# nfc-epd-eink.net
KiCad netlist of a schematic drawn in Altium Designer
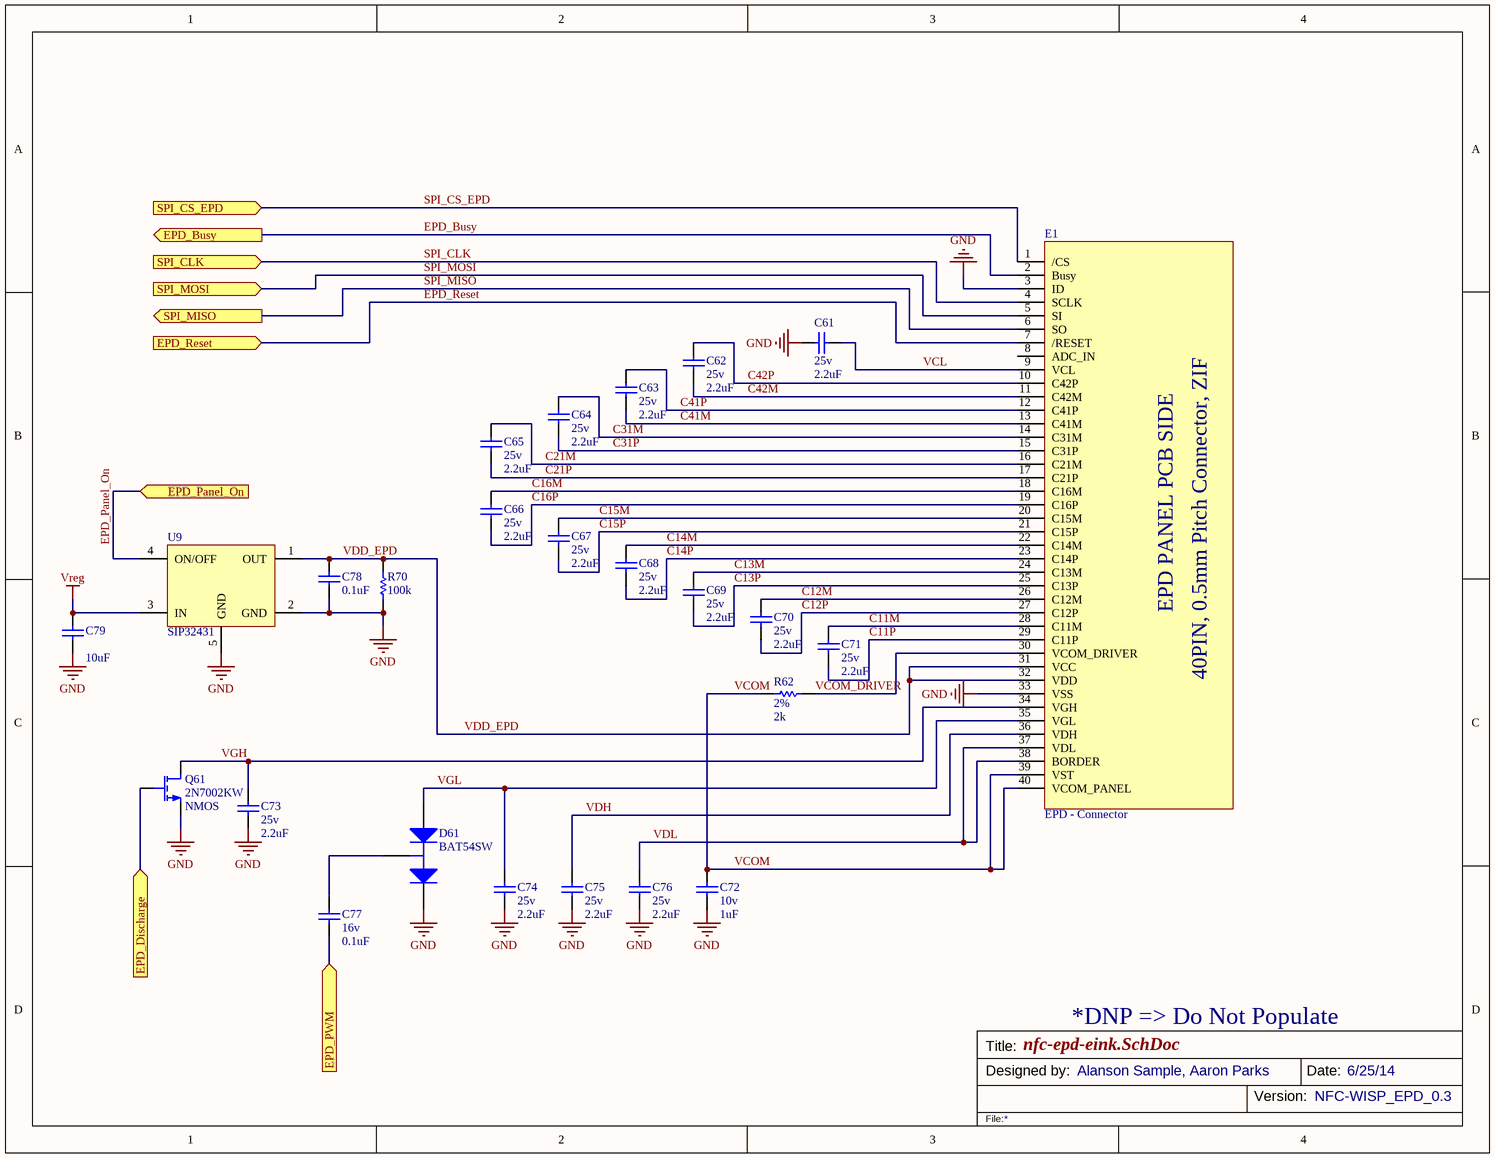
[diagram p0: nfc-epd-eink.SchDoc]

(export (version "E")
  (design (tool "Eeschema 10.0.6"))
  (components
    (comp (ref "C61")
      (value "2.2uF")
      (footprint "0402")
      (description "Ceramic Capacitor (Surface Mount)")
      (fields
        (field (name "MANUFACTURER") "Generic Ceramic Chip Cap (TBD)")
        (field (name "RATING") "25v")
        (field (name "Comment") "Cap")
      )
      (libsource (lib "WISP_AD10") (part "Cap"))
    )
    (comp (ref "C62")
      (value "2.2uF")
      (footprint "0402")
      (description "Ceramic Capacitor (Surface Mount)")
      (fields
        (field (name "MANUFACTURER") "Generic Ceramic Chip Cap (TBD)")
        (field (name "RATING") "25v")
        (field (name "Comment") "Cap")
      )
      (libsource (lib "WISP_AD10") (part "Cap"))
    )
    (comp (ref "C63")
      (value "2.2uF")
      (footprint "0402")
      (description "Ceramic Capacitor (Surface Mount)")
      (fields
        (field (name "MANUFACTURER") "Generic Ceramic Chip Cap (TBD)")
        (field (name "RATING") "25v")
        (field (name "Comment") "Cap")
      )
      (libsource (lib "WISP_AD10") (part "Cap"))
    )
    (comp (ref "C64")
      (value "2.2uF")
      (footprint "0402")
      (description "Ceramic Capacitor (Surface Mount)")
      (fields
        (field (name "MANUFACTURER") "Generic Ceramic Chip Cap (TBD)")
        (field (name "RATING") "25v")
        (field (name "Comment") "Cap")
      )
      (libsource (lib "WISP_AD10") (part "Cap"))
    )
    (comp (ref "C65")
      (value "2.2uF")
      (footprint "0402")
      (description "Ceramic Capacitor (Surface Mount)")
      (fields
        (field (name "MANUFACTURER") "Generic Ceramic Chip Cap (TBD)")
        (field (name "RATING") "25v")
        (field (name "Comment") "Cap")
      )
      (libsource (lib "WISP_AD10") (part "Cap"))
    )
    (comp (ref "C66")
      (value "2.2uF")
      (footprint "0402")
      (description "Ceramic Capacitor (Surface Mount)")
      (fields
        (field (name "MANUFACTURER") "Generic Ceramic Chip Cap (TBD)")
        (field (name "RATING") "25v")
        (field (name "Comment") "Cap")
      )
      (libsource (lib "WISP_AD10") (part "Cap"))
    )
    (comp (ref "C67")
      (value "2.2uF")
      (footprint "0402")
      (description "Ceramic Capacitor (Surface Mount)")
      (fields
        (field (name "MANUFACTURER") "Generic Ceramic Chip Cap (TBD)")
        (field (name "RATING") "25v")
        (field (name "Comment") "Cap")
      )
      (libsource (lib "WISP_AD10") (part "Cap"))
    )
    (comp (ref "C68")
      (value "2.2uF")
      (footprint "0402")
      (description "Ceramic Capacitor (Surface Mount)")
      (fields
        (field (name "MANUFACTURER") "Generic Ceramic Chip Cap (TBD)")
        (field (name "RATING") "25v")
        (field (name "Comment") "Cap")
      )
      (libsource (lib "WISP_AD10") (part "Cap"))
    )
    (comp (ref "C69")
      (value "2.2uF")
      (footprint "0402")
      (description "Ceramic Capacitor (Surface Mount)")
      (fields
        (field (name "MANUFACTURER") "Generic Ceramic Chip Cap (TBD)")
        (field (name "RATING") "25v")
        (field (name "Comment") "Cap")
      )
      (libsource (lib "WISP_AD10") (part "Cap"))
    )
    (comp (ref "C70")
      (value "2.2uF")
      (footprint "0402")
      (description "Ceramic Capacitor (Surface Mount)")
      (fields
        (field (name "MANUFACTURER") "Generic Ceramic Chip Cap (TBD)")
        (field (name "RATING") "25v")
        (field (name "Comment") "Cap")
      )
      (libsource (lib "WISP_AD10") (part "Cap"))
    )
    (comp (ref "C71")
      (value "2.2uF")
      (footprint "0402")
      (description "Ceramic Capacitor (Surface Mount)")
      (fields
        (field (name "MANUFACTURER") "Generic Ceramic Chip Cap (TBD)")
        (field (name "RATING") "25v")
        (field (name "Comment") "Cap")
      )
      (libsource (lib "WISP_AD10") (part "Cap"))
    )
    (comp (ref "C72")
      (value "1uF")
      (footprint "0402")
      (description "Ceramic Capacitor (Surface Mount)")
      (fields
        (field (name "MANUFACTURER") "Generic Ceramic Chip Cap (TBD)")
        (field (name "RATING") "10v")
        (field (name "Comment") "Cap")
      )
      (libsource (lib "WISP_AD10") (part "Cap"))
    )
    (comp (ref "C73")
      (value "2.2uF")
      (footprint "0402")
      (description "Ceramic Capacitor (Surface Mount)")
      (fields
        (field (name "MANUFACTURER") "Generic Ceramic Chip Cap (TBD)")
        (field (name "RATING") "25v")
        (field (name "Comment") "Cap")
      )
      (libsource (lib "WISP_AD10") (part "Cap"))
    )
    (comp (ref "C74")
      (value "2.2uF")
      (footprint "0402")
      (description "Ceramic Capacitor (Surface Mount)")
      (fields
        (field (name "MANUFACTURER") "Generic Ceramic Chip Cap (TBD)")
        (field (name "RATING") "25v")
        (field (name "Comment") "Cap")
      )
      (libsource (lib "WISP_AD10") (part "Cap"))
    )
    (comp (ref "C75")
      (value "2.2uF")
      (footprint "0402")
      (description "Ceramic Capacitor (Surface Mount)")
      (fields
        (field (name "MANUFACTURER") "Generic Ceramic Chip Cap (TBD)")
        (field (name "RATING") "25v")
        (field (name "Comment") "Cap")
      )
      (libsource (lib "WISP_AD10") (part "Cap"))
    )
    (comp (ref "C76")
      (value "2.2uF")
      (footprint "0402")
      (description "Ceramic Capacitor (Surface Mount)")
      (fields
        (field (name "MANUFACTURER") "Generic Ceramic Chip Cap (TBD)")
        (field (name "RATING") "25v")
        (field (name "Comment") "Cap")
      )
      (libsource (lib "WISP_AD10") (part "Cap"))
    )
    (comp (ref "C77")
      (value "0.1uF")
      (footprint "0402")
      (description "Ceramic Capacitor (Surface Mount)")
      (fields
        (field (name "MANUFACTURER") "Generic Ceramic Chip Cap (TBD)")
        (field (name "RATING") "16v")
        (field (name "Comment") "Cap")
      )
      (libsource (lib "WISP_AD10") (part "Cap"))
    )
    (comp (ref "C78")
      (value "0.1uF")
      (footprint "0402")
      (description "Ceramic Capacitor (Surface Mount)")
      (fields (field (name "MANUFACTURER") "Generic Ceramic Chip Cap (TBD)") (field (name "Comment") "Cap"))
      (libsource (lib "WISP_AD10") (part "Cap"))
    )
    (comp (ref "C79")
      (value "10uF")
      (footprint "0603")
      (description "Ceramic Capacitor (Surface Mount)")
      (fields (field (name "MANUFACTURER") "Generic Ceramic Chip Cap (TBD)") (field (name "Comment") "Cap"))
      (libsource (lib "WISP_AD10") (part "Cap"))
    )
    (comp (ref "D61")
      (value "BAT54SW")
      (footprint "SOT-323 / SC-70")
      (description "Diode Array, Two in Series, Small Package SOT-323")
      (fields
        (field (name "MANUFACTURER") "ON Semiconductor")
        (field (name "MANUFACTURER PART NUMBER") "BAT54SWT1G")
      )
      (libsource (lib "WISP_AD10") (part "Diode - Array_1"))
    )
    (comp (ref "E1")
      (value "EPD - Connector")
      (footprint "EPD - Connector")
      (description "FPC, 40pin, 0.5mm Pitch - ZIF")
      (fields
        (field (name "MANUFACTURER") "Hirose Electric Co Ltd")
        (field (name "MANUFACTURER PART NUMBER") "FH12-40S-0.5SH or FH12S-40S-0.5SH")
      )
      (libsource (lib "WISP_AD10") (part "EPD - Connector"))
    )
    (comp (ref "Q61")
      (value "2N7002KW")
      (footprint "SOT-323 / SC-70")
      (description "N-Channel MOSFET")
      (fields
        (field (name "DIGI-KEY PART NUMBER") "2N7002KWCT-ND")
        (field (name "MANUFACTURER") "Fairchild Semiconductor")
        (field (name "ALTIUM_VALUE") "NMOS")
      )
      (libsource (lib "WISP_AD10") (part "MOSFET-N"))
    )
    (comp (ref "R62")
      (value "2k")
      (footprint "0402")
      (description "Chip Resistor (Surface Mount)")
      (fields
        (field (name "MANUFACTURER") "Generic Chip Res (TBD)")
        (field (name "RATING") "2%")
        (field (name "Comment") "Res")
      )
      (libsource (lib "WISP_AD10") (part "Res"))
    )
    (comp (ref "R70")
      (value "100k")
      (footprint "0402")
      (description "Chip Resistor (Surface Mount)")
      (fields (field (name "MANUFACTURER") "Generic Chip Res (TBD)") (field (name "Comment") "Res"))
      (libsource (lib "WISP_AD10") (part "Res"))
    )
    (comp (ref "U9")
      (value "SIP32431")
      (footprint "TDFN-4")
      (description "High Sside Switch - 4TDFN package")
      (fields
        (field (name "DIGI-KEY PART NUMBER") "SIP32431DNP3-T1GE4CT-ND")
        (field (name "MANUFACTURER") "Vishay Siliconix")
      )
      (libsource (lib "WISP_AD10") (part "SIP32431"))
    )
  )
  (nets
    (net (code "1") (name "/C11M") (class "Default")
      (node (ref "C71") (pin "2") (pinfunction "2_2") (pintype "passive"))
      (node (ref "E1") (pin "28") (pinfunction "C11M_28") (pintype "passive"))
    )
    (net (code "2") (name "/C11P") (class "Default")
      (node (ref "C71") (pin "1") (pinfunction "1_1") (pintype "passive"))
      (node (ref "E1") (pin "29") (pinfunction "C11P_29") (pintype "passive"))
    )
    (net (code "3") (name "/C12M") (class "Default")
      (node (ref "C70") (pin "1") (pinfunction "1_1") (pintype "passive"))
      (node (ref "E1") (pin "26") (pinfunction "C12M_26") (pintype "passive"))
    )
    (net (code "4") (name "/C12P") (class "Default")
      (node (ref "C70") (pin "2") (pinfunction "2_2") (pintype "passive"))
      (node (ref "E1") (pin "27") (pinfunction "C12P_27") (pintype "passive"))
    )
    (net (code "5") (name "/C13M") (class "Default")
      (node (ref "C69") (pin "2") (pinfunction "2_2") (pintype "passive"))
      (node (ref "E1") (pin "24") (pinfunction "C13M_24") (pintype "passive"))
    )
    (net (code "6") (name "/C13P") (class "Default")
      (node (ref "C69") (pin "1") (pinfunction "1_1") (pintype "passive"))
      (node (ref "E1") (pin "25") (pinfunction "C13P_25") (pintype "passive"))
    )
    (net (code "7") (name "/C14M") (class "Default")
      (node (ref "C68") (pin "2") (pinfunction "2_2") (pintype "passive"))
      (node (ref "E1") (pin "22") (pinfunction "C14M_22") (pintype "passive"))
    )
    (net (code "8") (name "/C14P") (class "Default")
      (node (ref "C68") (pin "1") (pinfunction "1_1") (pintype "passive"))
      (node (ref "E1") (pin "23") (pinfunction "C14P_23") (pintype "passive"))
    )
    (net (code "9") (name "/C15M") (class "Default")
      (node (ref "C67") (pin "2") (pinfunction "2_2") (pintype "passive"))
      (node (ref "E1") (pin "20") (pinfunction "C15M_20") (pintype "passive"))
    )
    (net (code "10") (name "/C15P") (class "Default")
      (node (ref "C67") (pin "1") (pinfunction "1_1") (pintype "passive"))
      (node (ref "E1") (pin "21") (pinfunction "C15P_21") (pintype "passive"))
    )
    (net (code "11") (name "/C16M") (class "Default")
      (node (ref "C66") (pin "2") (pinfunction "2_2") (pintype "passive"))
      (node (ref "E1") (pin "18") (pinfunction "C16M_18") (pintype "passive"))
    )
    (net (code "12") (name "/C16P") (class "Default")
      (node (ref "C66") (pin "1") (pinfunction "1_1") (pintype "passive"))
      (node (ref "E1") (pin "19") (pinfunction "C16P_19") (pintype "passive"))
    )
    (net (code "13") (name "/C21M") (class "Default")
      (node (ref "C65") (pin "2") (pinfunction "2_2") (pintype "passive"))
      (node (ref "E1") (pin "16") (pinfunction "C21M_16") (pintype "passive"))
    )
    (net (code "14") (name "/C21P") (class "Default")
      (node (ref "C65") (pin "1") (pinfunction "1_1") (pintype "passive"))
      (node (ref "E1") (pin "17") (pinfunction "C21P_17") (pintype "passive"))
    )
    (net (code "15") (name "/C31M") (class "Default")
      (node (ref "C64") (pin "2") (pinfunction "2_2") (pintype "passive"))
      (node (ref "E1") (pin "14") (pinfunction "C31M_14") (pintype "passive"))
    )
    (net (code "16") (name "/C31P") (class "Default")
      (node (ref "C64") (pin "1") (pinfunction "1_1") (pintype "passive"))
      (node (ref "E1") (pin "15") (pinfunction "C31P_15") (pintype "passive"))
    )
    (net (code "17") (name "/C41M") (class "Default")
      (node (ref "C63") (pin "1") (pinfunction "1_1") (pintype "passive"))
      (node (ref "E1") (pin "13") (pinfunction "C41M_13") (pintype "passive"))
    )
    (net (code "18") (name "/C41P") (class "Default")
      (node (ref "C63") (pin "2") (pinfunction "2_2") (pintype "passive"))
      (node (ref "E1") (pin "12") (pinfunction "C41P_12") (pintype "passive"))
    )
    (net (code "19") (name "/C42M") (class "Default")
      (node (ref "C62") (pin "2") (pinfunction "2_2") (pintype "passive"))
      (node (ref "E1") (pin "11") (pinfunction "C42M_11") (pintype "passive"))
    )
    (net (code "20") (name "/C42P") (class "Default")
      (node (ref "C62") (pin "1") (pinfunction "1_1") (pintype "passive"))
      (node (ref "E1") (pin "10") (pinfunction "C42P_10") (pintype "passive"))
    )
    (net (code "21") (name "/EPD_Busy") (class "Default")
      (node (ref "E1") (pin "2") (pinfunction "Busy_2") (pintype "passive"))
    )
    (net (code "22") (name "/EPD_Discharge") (class "Default")
      (node (ref "Q61") (pin "1") (pinfunction "G_1") (pintype "passive"))
    )
    (net (code "23") (name "/EPD_PWM") (class "Default")
      (node (ref "C77") (pin "1") (pinfunction "1_1") (pintype "passive"))
    )
    (net (code "24") (name "/EPD_Panel_On") (class "Default")
      (node (ref "U9") (pin "4") (pinfunction "ON/OFF_4") (pintype "passive"))
    )
    (net (code "25") (name "/EPD_Reset") (class "Default")
      (node (ref "E1") (pin "7") (pinfunction "/RESET_7") (pintype "passive"))
    )
    (net (code "26") (name "/SPI_CLK") (class "Default")
      (node (ref "E1") (pin "4") (pinfunction "SCLK_4") (pintype "passive"))
    )
    (net (code "27") (name "/SPI_CS_EPD") (class "Default")
      (node (ref "E1") (pin "1") (pinfunction "/CS_1") (pintype "passive"))
    )
    (net (code "28") (name "/SPI_MISO") (class "Default")
      (node (ref "E1") (pin "6") (pinfunction "SO_6") (pintype "passive"))
    )
    (net (code "29") (name "/SPI_MOSI") (class "Default")
      (node (ref "E1") (pin "5") (pinfunction "SI_5") (pintype "passive"))
    )
    (net (code "30") (name "/VCL") (class "Default")
      (node (ref "C61") (pin "1") (pinfunction "1_1") (pintype "passive"))
      (node (ref "E1") (pin "9") (pinfunction "VCL_9") (pintype "passive"))
    )
    (net (code "31") (name "/VCOM") (class "Default")
      (node (ref "C72") (pin "2") (pinfunction "2_2") (pintype "passive"))
      (node (ref "E1") (pin "39") (pinfunction "VST_39") (pintype "passive"))
      (node (ref "E1") (pin "40") (pinfunction "VCOM_PANEL_40") (pintype "passive"))
      (node (ref "R62") (pin "2") (pinfunction "2_2") (pintype "passive"))
    )
    (net (code "32") (name "/VCOM_DRIVER") (class "Default")
      (node (ref "E1") (pin "30") (pinfunction "VCOM_DRIVER_30") (pintype "passive"))
      (node (ref "R62") (pin "1") (pinfunction "1_1") (pintype "passive"))
    )
    (net (code "33") (name "/VDD_EPD") (class "Default")
      (node (ref "C78") (pin "2") (pinfunction "2_2") (pintype "passive"))
      (node (ref "E1") (pin "31") (pinfunction "VCC_31") (pintype "passive"))
      (node (ref "E1") (pin "32") (pinfunction "VDD_32") (pintype "passive"))
      (node (ref "R70") (pin "2") (pinfunction "2_2") (pintype "passive"))
      (node (ref "U9") (pin "1") (pinfunction "OUT_1") (pintype "passive"))
    )
    (net (code "34") (name "/VDH") (class "Default")
      (node (ref "C75") (pin "2") (pinfunction "2_2") (pintype "passive"))
      (node (ref "E1") (pin "36") (pinfunction "VDH_36") (pintype "passive"))
    )
    (net (code "35") (name "/VDL") (class "Default")
      (node (ref "C76") (pin "2") (pinfunction "2_2") (pintype "passive"))
      (node (ref "E1") (pin "37") (pinfunction "VDL_37") (pintype "passive"))
      (node (ref "E1") (pin "38") (pinfunction "BORDER_38") (pintype "passive"))
    )
    (net (code "36") (name "/VGH") (class "Default")
      (node (ref "C73") (pin "2") (pinfunction "2_2") (pintype "passive"))
      (node (ref "E1") (pin "34") (pinfunction "VGH_34") (pintype "passive"))
      (node (ref "Q61") (pin "3") (pinfunction "D_3") (pintype "passive"))
    )
    (net (code "37") (name "/VGL") (class "Default")
      (node (ref "C74") (pin "2") (pinfunction "2_2") (pintype "passive"))
      (node (ref "D61") (pin "1") (pinfunction "A_1") (pintype "passive"))
      (node (ref "E1") (pin "35") (pinfunction "VGL_35") (pintype "passive"))
    )
    (net (code "38") (name "GND") (class "Default")
      (node (ref "C61") (pin "2") (pinfunction "2_2") (pintype "passive"))
      (node (ref "C72") (pin "1") (pinfunction "1_1") (pintype "passive"))
      (node (ref "C73") (pin "1") (pinfunction "1_1") (pintype "passive"))
      (node (ref "C74") (pin "1") (pinfunction "1_1") (pintype "passive"))
      (node (ref "C75") (pin "1") (pinfunction "1_1") (pintype "passive"))
      (node (ref "C76") (pin "1") (pinfunction "1_1") (pintype "passive"))
      (node (ref "C78") (pin "1") (pinfunction "1_1") (pintype "passive"))
      (node (ref "C79") (pin "1") (pinfunction "1_1") (pintype "passive"))
      (node (ref "D61") (pin "2") (pinfunction "K_2") (pintype "passive"))
      (node (ref "E1") (pin "3") (pinfunction "ID_3") (pintype "passive"))
      (node (ref "E1") (pin "33") (pinfunction "VSS_33") (pintype "passive"))
      (node (ref "Q61") (pin "2") (pinfunction "S_2") (pintype "passive"))
      (node (ref "R70") (pin "1") (pinfunction "1_1") (pintype "passive"))
      (node (ref "U9") (pin "2") (pinfunction "GND_2") (pintype "passive"))
      (node (ref "U9") (pin "5") (pinfunction "GND_5") (pintype "passive"))
    )
    (net (code "39") (name "Net-(D61-C)") (class "Default")
      (node (ref "C77") (pin "2") (pinfunction "2_2") (pintype "passive"))
      (node (ref "D61") (pin "3") (pinfunction "C_3") (pintype "passive"))
    )
    (net (code "40") (name "Vreg") (class "Default")
      (node (ref "C79") (pin "2") (pinfunction "2_2") (pintype "passive"))
      (node (ref "U9") (pin "3") (pinfunction "IN_3") (pintype "passive"))
    )
    (net (code "41") (name "unconnected-(E1-ADC_IN-Pad8)") (class "Default")
      (node (ref "E1") (pin "8") (pinfunction "ADC_IN_8") (pintype "passive"))
    )
  )
)
